# RFStamp.net
KiCad netlist of a schematic drawn in Altium Designer
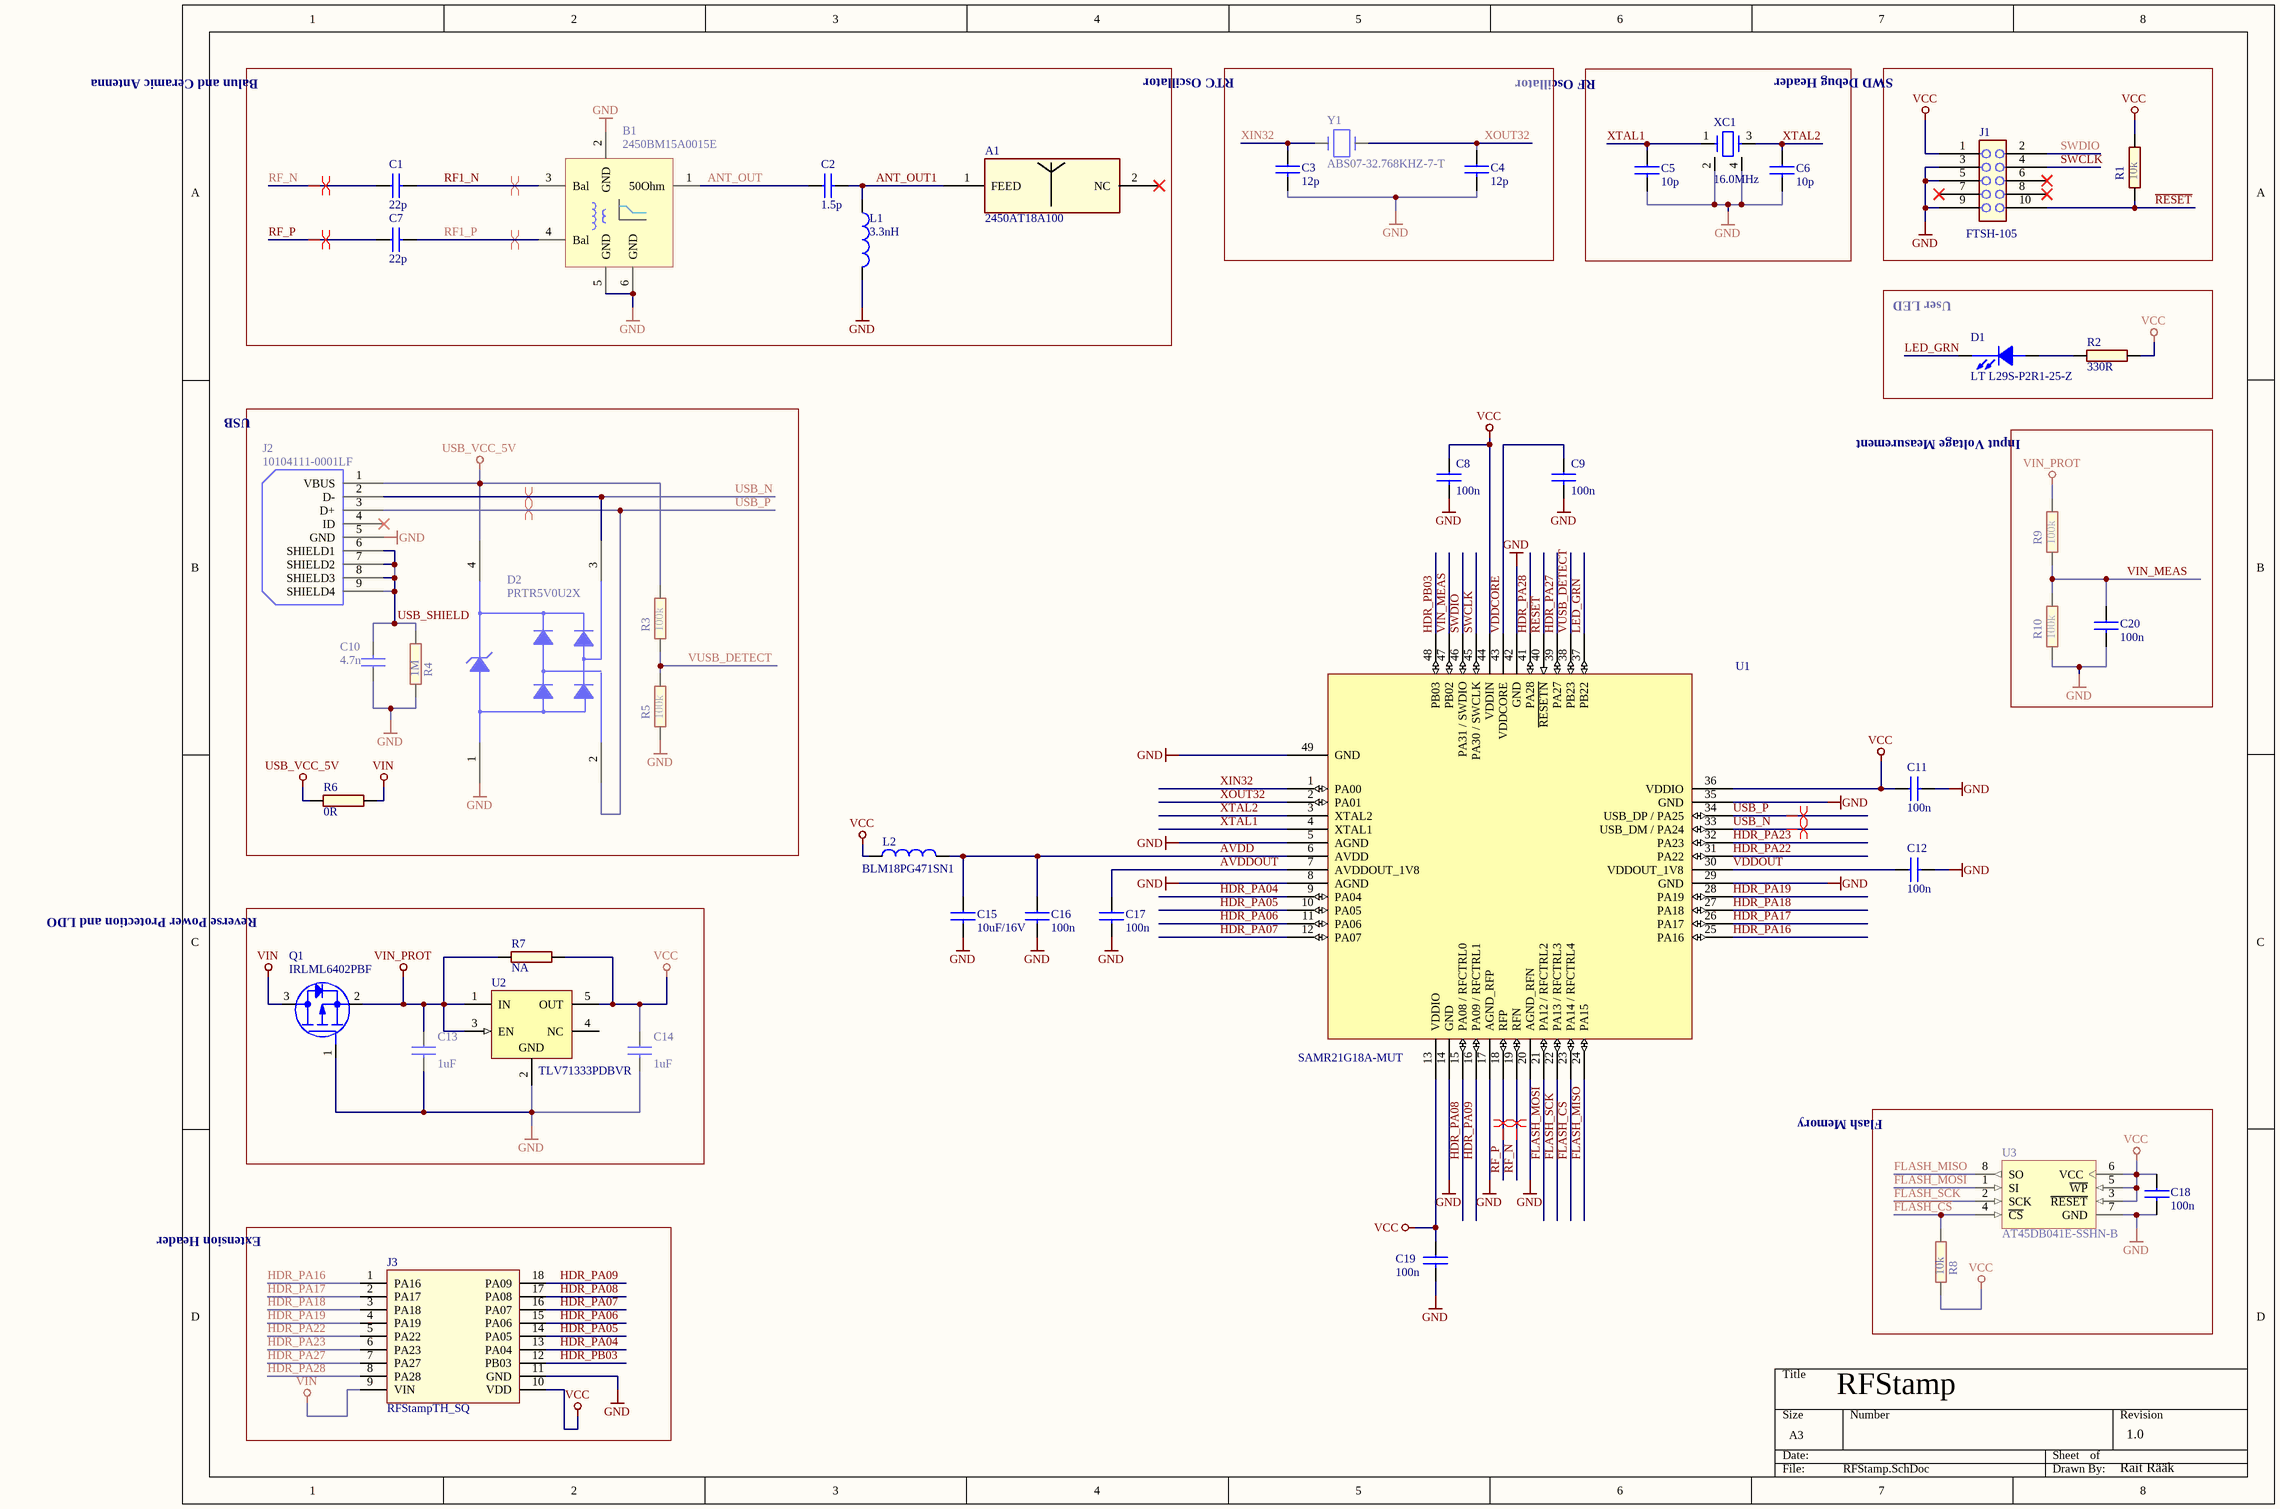
[diagram p0: RFStamp.SchDoc]

(export (version "E")
  (design (tool "Eeschema 10.0.6"))
  (components
    (comp (ref "A1")
      (value "2450AT18A100")
      (footprint "2450AT18A100")
      (description "Ceramic 2.45 GHz Antenna")
      (libsource (lib "Johanson Technology") (part "2450AT18A100"))
    )
    (comp (ref "B1")
      (value "2450BM15A0015E")
      (footprint "SAMR21_Xplained_Pro:AP3-00060")
      (description "Filtered Balun to match AT86RF232/233 (35288)")
      (fields (field (name "MANUFACTURER") "Johanson Technology"))
      (libsource (lib "AltiumDbLib") (part "FilterBalun_NoFeed"))
    )
    (comp (ref "C1")
      (value "22p")
      (footprint "AP1-00053")
      (description "Ceramic capacitor, SMD 0402, X7R, 16V, +/-10%")
      (fields (field (name "TOLERANCE") "16V, +/-10%") (field (name "MANUFACTURER") "Kemet"))
      (libsource (lib "AltiumDbLib") (part "CAP-NONPOL"))
    )
    (comp (ref "C2")
      (value "1.5p")
      (footprint "AP1-00053")
      (description "Ceramic capacitor, SMD 0402, X7R, 16V, +/-10%")
      (fields (field (name "TOLERANCE") "16V, +/-10%") (field (name "MANUFACTURER") "Kemet"))
      (libsource (lib "AltiumDbLib") (part "CAP-NONPOL"))
    )
    (comp (ref "C3")
      (value "12p")
      (footprint "AP1-00053")
      (description "Ceramic capacitor, SMD 0402, X7R, 16V, +/-10%")
      (fields (field (name "TOLERANCE") "16V, +/-10%") (field (name "MANUFACTURER") "Kemet"))
      (libsource (lib "AltiumDbLib") (part "CAP-NONPOL"))
    )
    (comp (ref "C4")
      (value "12p")
      (footprint "AP1-00053")
      (description "Ceramic capacitor, SMD 0402, X7R, 16V, +/-10%")
      (fields (field (name "TOLERANCE") "16V, +/-10%") (field (name "MANUFACTURER") "Kemet"))
      (libsource (lib "AltiumDbLib") (part "CAP-NONPOL"))
    )
    (comp (ref "C5")
      (value "10p")
      (footprint "AP1-00053")
      (description "Ceramic capacitor, SMD 0402, X7R, 16V, +/-10%")
      (fields (field (name "TOLERANCE") "16V, +/-10%") (field (name "MANUFACTURER") "Kemet"))
      (libsource (lib "AltiumDbLib") (part "CAP-NONPOL"))
    )
    (comp (ref "C6")
      (value "10p")
      (footprint "AP1-00053")
      (description "Ceramic capacitor, SMD 0402, X7R, 16V, +/-10%")
      (fields (field (name "TOLERANCE") "16V, +/-10%") (field (name "MANUFACTURER") "Kemet"))
      (libsource (lib "AltiumDbLib") (part "CAP-NONPOL"))
    )
    (comp (ref "C7")
      (value "22p")
      (footprint "AP1-00053")
      (description "Ceramic capacitor, SMD 0402, X7R, 16V, +/-10%")
      (fields (field (name "TOLERANCE") "16V, +/-10%") (field (name "MANUFACTURER") "Kemet"))
      (libsource (lib "AltiumDbLib") (part "CAP-NONPOL"))
    )
    (comp (ref "C8")
      (value "100n")
      (footprint "AP1-00053")
      (description "Ceramic capacitor, SMD 0402, X7R, 16V, +/-10%")
      (fields
        (field (name "TOLERANCE") "16V, +/-10%")
        (field (name "MANUFACTURER") "Kemet")
        (field (name "VERIFIED BY") "Lars Helge Mo")
      )
      (libsource (lib "AltiumDbLib") (part "CAP-NONPOL"))
    )
    (comp (ref "C9")
      (value "100n")
      (footprint "AP1-00053")
      (description "Ceramic capacitor, SMD 0402, X7R, 16V, +/-10%")
      (fields
        (field (name "TOLERANCE") "16V, +/-10%")
        (field (name "MANUFACTURER") "Kemet")
        (field (name "VERIFIED BY") "Lars Helge Mo")
      )
      (libsource (lib "AltiumDbLib") (part "CAP-NONPOL"))
    )
    (comp (ref "C10")
      (value "4.7n")
      (footprint "SAMR21_Xplained_Pro:AP1-00053")
      (description "Ceramic capacitor, SMD 0402, X7R, 25V, +/-10%")
      (fields (field (name "TOLERANCE") "25V, +/-10%"))
      (libsource (lib "AltiumDbLib") (part "CAP-NONPOL"))
    )
    (comp (ref "C11")
      (value "100n")
      (footprint "AP1-00053")
      (description "Ceramic capacitor, SMD 0402, X7R, 16V, +/-10%")
      (fields (field (name "TOLERANCE") "16V, +/-10%") (field (name "MANUFACTURER") "Kemet"))
      (libsource (lib "AltiumDbLib") (part "CAP-NONPOL"))
    )
    (comp (ref "C12")
      (value "100n")
      (footprint "AP1-00053")
      (description "Ceramic capacitor, SMD 0402, X7R, 16V, +/-10%")
      (fields (field (name "TOLERANCE") "16V, +/-10%") (field (name "MANUFACTURER") "Kemet"))
      (libsource (lib "AltiumDbLib") (part "CAP-NONPOL"))
    )
    (comp (ref "C13")
      (value "1uF")
      (footprint "SAMR21_Xplained_Pro:AP1-00039")
      (description "Ceramic capacitor, SMD 0603, X5R, 10V, 10% (de31036)")
      (fields (field (name "TOLERANCE") "10%") (field (name "MANUFACTURER") "tdk"))
      (libsource (lib "AltiumDbLib") (part "CAP-NONPOL"))
    )
    (comp (ref "C14")
      (value "1uF")
      (footprint "SAMR21_Xplained_Pro:AP1-00039")
      (description "Ceramic capacitor, SMD 0603, X5R, 6.3V, 10%")
      (fields (field (name "TOLERANCE") "10%") (field (name "MANUFACTURER") "tdk"))
      (libsource (lib "AltiumDbLib") (part "CAP-NONPOL"))
    )
    (comp (ref "C15")
      (value "10uF/16V")
      (footprint "SAMR21_Xplained_Pro:AP1-00039")
      (description "Ceramic capacitor, SMD 0603, X5R, 16V, 10UF ± 20% (High Density)")
      (fields (field (name "MANUFACTURER") "Taiyo Yuden") (field (name "MPN") "EMK107BBJ106MA-T"))
      (libsource (lib "AltiumDbLib") (part "CAP-NONPOL"))
    )
    (comp (ref "C16")
      (value "100n")
      (footprint "AP1-00053")
      (description "Ceramic capacitor, SMD 0402, X7R, 16V, +/-10%")
      (fields (field (name "TOLERANCE") "16V, +/-10%") (field (name "MANUFACTURER") "Kemet"))
      (libsource (lib "AltiumDbLib") (part "CAP-NONPOL"))
    )
    (comp (ref "C17")
      (value "100n")
      (footprint "AP1-00053")
      (description "Ceramic capacitor, SMD 0402, X7R, 16V, +/-10%")
      (fields (field (name "TOLERANCE") "16V, +/-10%") (field (name "MANUFACTURER") "Kemet"))
      (libsource (lib "AltiumDbLib") (part "CAP-NONPOL"))
    )
    (comp (ref "C18")
      (value "100n")
      (footprint "AP1-00053")
      (description "Ceramic capacitor, SMD 0402, X7R, 16V, +/-10%")
      (fields (field (name "TOLERANCE") "16V, +/-10%") (field (name "MANUFACTURER") "Kemet"))
      (libsource (lib "AltiumDbLib") (part "CAP-NONPOL"))
    )
    (comp (ref "C19")
      (value "100n")
      (footprint "AP1-00053")
      (description "Ceramic capacitor, SMD 0402, X7R, 16V, +/-10%")
      (fields (field (name "TOLERANCE") "16V, +/-10%") (field (name "MANUFACTURER") "Kemet"))
      (libsource (lib "AltiumDbLib") (part "CAP-NONPOL"))
    )
    (comp (ref "C20")
      (value "100n")
      (footprint "AP1-00053")
      (description "Ceramic capacitor, SMD 0402, X7R, 16V, +/-10%")
      (fields (field (name "TOLERANCE") "16V, +/-10%") (field (name "MANUFACTURER") "Kemet"))
      (libsource (lib "AltiumDbLib") (part "CAP-NONPOL"))
    )
    (comp (ref "D1")
      (value "LT L29S-P2R1-25-Z")
      (footprint "Osram:LS L29K")
      (libsource (lib "Osram") (part "LS L29K"))
    )
    (comp (ref "D2")
      (value "PRTR5V0U2X")
      (footprint "SAMR21_Xplained_Pro:AP4-00001")
      (description "Double rail-to-rail USB ESD protection diode")
      (fields (field (name "MANUFACTURER") "Philips"))
      (libsource (lib "AltiumDbLib") (part "PRTR5V0U2X"))
    )
    (comp (ref "J1")
      (value "FTSH-105")
      (footprint "Samtec:FTSH_SMT_10")
      (description "CONN HEADER 10POS DUAL .05\" SMD")
      (libsource (lib "Samtec") (part "FTSH-105"))
    )
    (comp (ref "J2")
      (value "10104111-0001LF")
      (footprint "SAMR21_Xplained_Pro:AP8-00604")
      (description "Micro USB AB Connector")
      (fields (field (name "MANUFACTURER") "FCI"))
      (libsource (lib "AltiumDbLib") (part "USB_AB"))
    )
    (comp (ref "J3")
      (value "RFStampTH_SQ")
      (footprint "RFSTAMP_TH_SQ")
      (libsource (lib "MyLib") (part "RFStampTH_SQ"))
    )
    (comp (ref "L1")
      (value "3.3nH")
      (footprint "0402-A")
      (description "Inductor")
      (libsource (lib "Miscellaneous Devices") (part "Inductor"))
    )
    (comp (ref "L2")
      (value "BLM18PG471SN1")
      (footprint "SAMR21_Xplained_Pro:AP3-00005")
      (description "SMD RF inductor 0603. Z=470Ohm (@100MHz), Max R(dc)=0.65Ohm, Max current=1A")
      (fields (field (name "TOLERANCE") "±25%") (field (name "MANUFACTURER") "Murata"))
      (libsource (lib "AltiumDbLib") (part "INDUCTOR"))
    )
    (comp (ref "Q1")
      (value "IRLML6402PBF")
      (footprint "AP5-00002")
      (description "P-ch. MOSFET. -30V, -3.7A continuous,RDS(ON)=0.05Ohm@VGS=-4,5V, RDS(ON)=0.08Ohm@VGS=-2.5V")
      (fields (field (name "MANUFACTURER") "International Rectifier"))
      (libsource (lib "AltiumDbLib") (part "MOSFET_P_GSD"))
    )
    (comp (ref "R1")
      (value "10k")
      (footprint "AP2-00011")
      (description "Thick film resistor, SMD 0402, 1/16W, 5%")
      (fields (field (name "TOLERANCE") "5 %"))
      (libsource (lib "") (part "R2_2"))
    )
    (comp (ref "R2")
      (value "330R")
      (footprint "AP2-00011")
      (description "Thick film resistor, SMD 0402, 1/16W, 5%")
      (fields (field (name "TOLERANCE") "5 %"))
      (libsource (lib "") (part "R2_3"))
    )
    (comp (ref "R3")
      (value "100k")
      (footprint "AP2-00011")
      (description "Thick film resistor, SMD 0402, 1/16W, 5%")
      (fields (field (name "TOLERANCE") "5 %"))
      (libsource (lib "") (part "R2_2"))
    )
    (comp (ref "R4")
      (value "1M")
      (footprint "SAMR21_Xplained_Pro:AP2-00011")
      (description "Thick film resistor, SMD 0402, 1/16W, 5%")
      (fields (field (name "TOLERANCE") "5 %") (field (name "MANUFACTURER") "KOA"))
      (libsource (lib "AltiumDbLib") (part "R2"))
    )
    (comp (ref "R5")
      (value "100k")
      (footprint "AP2-00011")
      (description "Thick film resistor, SMD 0402, 1/16W, 5%")
      (fields (field (name "TOLERANCE") "5 %"))
      (libsource (lib "") (part "R2_2"))
    )
    (comp (ref "R6")
      (value "0R")
      (footprint "AP2-00011")
      (description "Thick film resistor, SMD 0402, 1/16W, 5%")
      (fields (field (name "TOLERANCE") "5 %"))
      (libsource (lib "") (part "R2_1"))
    )
    (comp (ref "R7")
      (value "NA")
      (footprint "AP2-00011")
      (description "Thick film resistor, SMD 0402, 1/16W, 5%")
      (fields (field (name "TOLERANCE") "5 %") (field (name "Comment") "0R"))
      (libsource (lib "") (part "R2_1"))
    )
    (comp (ref "R8")
      (value "10k")
      (footprint "SAMR21_Xplained_Pro:AP2-00011")
      (description "Thick film resistor, SMD 0402, 1/16W, 5%")
      (fields (field (name "TOLERANCE") "5 %") (field (name "MANUFACTURER") "KOA"))
      (libsource (lib "AltiumDbLib") (part "R2"))
    )
    (comp (ref "R9")
      (value "100k")
      (footprint "AP2-00011")
      (description "Thick film resistor, SMD 0402, 1/16W, 5%")
      (fields (field (name "TOLERANCE") "5 %"))
      (libsource (lib "") (part "R2_2"))
    )
    (comp (ref "R10")
      (value "100k")
      (footprint "AP2-00011")
      (description "Thick film resistor, SMD 0402, 1/16W, 5%")
      (fields (field (name "TOLERANCE") "5 %"))
      (libsource (lib "") (part "R2_2"))
    )
    (comp (ref "U1")
      (value "SAMR21G18A-MUT")
      (footprint "AP6-00171")
      (description "Atmel 32-bit Cortex M0+ MCU with RF233 SIP.")
      (fields (field (name "MANUFACTURER") "ATMEL"))
      (libsource (lib "MyLib") (part "SAMR21G"))
    )
    (comp (ref "U2")
      (value "TLV71333PDBVR")
      (footprint "TI-DBV5_N")
      (fields (field (name "MANUFACTURER") "Texas Instruments"))
      (libsource (lib "TI Power Management Linear Regulator Single Channel LDO (0-350mA)") (part "TLV70233DBVR"))
    )
    (comp (ref "U3")
      (value "AT45DB041E-SSHN-B")
      (footprint "8S1_N")
      (description "4-Mbit DataFlash (with Extra 128-Kbits), 1.65V Minimum SPI Serial Flash Memory, 8-Pin SOIC")
      (libsource (lib "Atmel") (part "AT45DB041E"))
    )
    (comp (ref "XC1")
      (value "16.0MHz")
      (footprint "AP7-00061")
      (description "16MHz uXtal, 3.2 x 2.5 mm SMD, CL=9pF, 15PPM, ESR=80ohm(Max.")
      (fields (field (name "TOLERANCE") "15ppm") (field (name "MANUFACTURER") "Epson Toyocom"))
      (libsource (lib "MyLib") (part "TSX-3225"))
    )
    (comp (ref "Y1")
      (value "ABS07-32.768KHZ-7-T")
      (footprint "ABS07")
      (description "Low Profile Surface Mount Crystal")
      (libsource (lib "Abracon") (part "ABS07"))
    )
  )
  (nets
    (net (code "1") (name "/ANT_OUT") (class "Default")
      (node (ref "B1") (pin "1") (pinfunction "50Ohm_1") (pintype "passive"))
      (node (ref "C2") (pin "1") (pinfunction "1_1") (pintype "passive"))
    )
    (net (code "2") (name "/ANT_OUT1") (class "Default")
      (node (ref "A1") (pin "1") (pinfunction "FEED_1") (pintype "passive"))
      (node (ref "C2") (pin "2") (pinfunction "2_2") (pintype "passive"))
      (node (ref "L1") (pin "1") (pinfunction "1_1") (pintype "passive"))
    )
    (net (code "3") (name "/AVDD") (class "Default")
      (node (ref "C15") (pin "1") (pinfunction "1_1") (pintype "passive"))
      (node (ref "C16") (pin "1") (pinfunction "1_1") (pintype "passive"))
      (node (ref "L2") (pin "2") (pinfunction "2_2") (pintype "passive"))
      (node (ref "U1") (pin "6") (pinfunction "AVDD_6") (pintype "power_in"))
    )
    (net (code "4") (name "/AVDDOUT") (class "Default")
      (node (ref "C17") (pin "1") (pinfunction "1_1") (pintype "passive"))
      (node (ref "U1") (pin "7") (pinfunction "AVDDOUT_1V8_7") (pintype "power_in"))
    )
    (net (code "5") (name "/FLASH_MISO") (class "Default")
      (node (ref "U1") (pin "24") (pinfunction "PA15_24") (pintype "bidirectional"))
      (node (ref "U3") (pin "8") (pinfunction "SO_8") (pintype "output"))
    )
    (net (code "6") (name "/FLASH_MOSI") (class "Default")
      (node (ref "U1") (pin "21") (pinfunction "PA12_/_RFCTRL2_21") (pintype "bidirectional"))
      (node (ref "U3") (pin "1") (pinfunction "SI_1") (pintype "input"))
    )
    (net (code "7") (name "/FLASH_SCK") (class "Default")
      (node (ref "U1") (pin "22") (pinfunction "PA13_/_RFCTRL3_22") (pintype "bidirectional"))
      (node (ref "U3") (pin "2") (pinfunction "SCK_2") (pintype "input"))
    )
    (net (code "8") (name "/HDR_PA04") (class "Default")
      (node (ref "J3") (pin "13") (pinfunction "PA04_13") (pintype "passive"))
      (node (ref "U1") (pin "9") (pinfunction "PA04_9") (pintype "bidirectional"))
    )
    (net (code "9") (name "/HDR_PA05") (class "Default")
      (node (ref "J3") (pin "14") (pinfunction "PA05_14") (pintype "passive"))
      (node (ref "U1") (pin "10") (pinfunction "PA05_10") (pintype "bidirectional"))
    )
    (net (code "10") (name "/HDR_PA06") (class "Default")
      (node (ref "J3") (pin "15") (pinfunction "PA06_15") (pintype "passive"))
      (node (ref "U1") (pin "11") (pinfunction "PA06_11") (pintype "bidirectional"))
    )
    (net (code "11") (name "/HDR_PA07") (class "Default")
      (node (ref "J3") (pin "16") (pinfunction "PA07_16") (pintype "passive"))
      (node (ref "U1") (pin "12") (pinfunction "PA07_12") (pintype "bidirectional"))
    )
    (net (code "12") (name "/HDR_PA08") (class "Default")
      (node (ref "J3") (pin "17") (pinfunction "PA08_17") (pintype "passive"))
      (node (ref "U1") (pin "15") (pinfunction "PA08_/_RFCTRL0_15") (pintype "bidirectional"))
    )
    (net (code "13") (name "/HDR_PA09") (class "Default")
      (node (ref "J3") (pin "18") (pinfunction "PA09_18") (pintype "passive"))
      (node (ref "U1") (pin "16") (pinfunction "PA09_/_RFCTRL1_16") (pintype "bidirectional"))
    )
    (net (code "14") (name "/HDR_PA16") (class "Default")
      (node (ref "J3") (pin "1") (pinfunction "PA16_1") (pintype "passive"))
      (node (ref "U1") (pin "25") (pinfunction "PA16_25") (pintype "bidirectional"))
    )
    (net (code "15") (name "/HDR_PA17") (class "Default")
      (node (ref "J3") (pin "2") (pinfunction "PA17_2") (pintype "passive"))
      (node (ref "U1") (pin "26") (pinfunction "PA17_26") (pintype "bidirectional"))
    )
    (net (code "16") (name "/HDR_PA18") (class "Default")
      (node (ref "J3") (pin "3") (pinfunction "PA18_3") (pintype "passive"))
      (node (ref "U1") (pin "27") (pinfunction "PA18_27") (pintype "bidirectional"))
    )
    (net (code "17") (name "/HDR_PA19") (class "Default")
      (node (ref "J3") (pin "4") (pinfunction "PA19_4") (pintype "passive"))
      (node (ref "U1") (pin "28") (pinfunction "PA19_28") (pintype "bidirectional"))
    )
    (net (code "18") (name "/HDR_PA22") (class "Default")
      (node (ref "J3") (pin "5") (pinfunction "PA22_5") (pintype "passive"))
      (node (ref "U1") (pin "31") (pinfunction "PA22_31") (pintype "bidirectional"))
    )
    (net (code "19") (name "/HDR_PA23") (class "Default")
      (node (ref "J3") (pin "6") (pinfunction "PA23_6") (pintype "passive"))
      (node (ref "U1") (pin "32") (pinfunction "PA23_32") (pintype "bidirectional"))
    )
    (net (code "20") (name "/HDR_PA27") (class "Default")
      (node (ref "J3") (pin "7") (pinfunction "PA27_7") (pintype "passive"))
      (node (ref "U1") (pin "39") (pinfunction "PA27_39") (pintype "bidirectional"))
    )
    (net (code "21") (name "/HDR_PA28") (class "Default")
      (node (ref "J3") (pin "8") (pinfunction "PA28_8") (pintype "passive"))
      (node (ref "U1") (pin "41") (pinfunction "PA28_41") (pintype "bidirectional"))
    )
    (net (code "22") (name "/HDR_PB03") (class "Default")
      (node (ref "J3") (pin "12") (pinfunction "PB03_12") (pintype "passive"))
      (node (ref "U1") (pin "48") (pinfunction "PB03_48") (pintype "bidirectional"))
    )
    (net (code "23") (name "/LED_GRN") (class "Default")
      (node (ref "D1") (pin "1") (pinfunction "CATHODE_1") (pintype "passive"))
      (node (ref "U1") (pin "37") (pinfunction "PB22_37") (pintype "bidirectional"))
    )
    (net (code "24") (name "/RF1_N") (class "Default")
      (node (ref "B1") (pin "3") (pinfunction "Bal_3") (pintype "passive"))
      (node (ref "C1") (pin "2") (pinfunction "2_2") (pintype "passive"))
    )
    (net (code "25") (name "/RF1_P") (class "Default")
      (node (ref "B1") (pin "4") (pinfunction "Bal_4") (pintype "passive"))
      (node (ref "C7") (pin "2") (pinfunction "2_2") (pintype "passive"))
    )
    (net (code "26") (name "/RF_N") (class "Default")
      (node (ref "C1") (pin "1") (pinfunction "1_1") (pintype "passive"))
      (node (ref "U1") (pin "19") (pinfunction "RFN_19") (pintype "bidirectional"))
    )
    (net (code "27") (name "/RF_P") (class "Default")
      (node (ref "C7") (pin "1") (pinfunction "1_1") (pintype "passive"))
      (node (ref "U1") (pin "18") (pinfunction "RFP_18") (pintype "bidirectional"))
    )
    (net (code "28") (name "/SWCLK") (class "Default")
      (node (ref "J1") (pin "4") (pinfunction "4_4") (pintype "passive"))
      (node (ref "U1") (pin "45") (pinfunction "PA30_/_SWCLK_45") (pintype "bidirectional"))
    )
    (net (code "29") (name "/SWDIO") (class "Default")
      (node (ref "J1") (pin "2") (pinfunction "2_2") (pintype "passive"))
      (node (ref "U1") (pin "46") (pinfunction "PA31_/_SWDIO_46") (pintype "bidirectional"))
    )
    (net (code "30") (name "/USB_N") (class "Default")
      (node (ref "D2") (pin "3") (pinfunction "I/O_2_3") (pintype "passive"))
      (node (ref "J2") (pin "2") (pinfunction "D-_2") (pintype "passive"))
      (node (ref "U1") (pin "33") (pinfunction "USB_DM_/_PA24_33") (pintype "bidirectional"))
    )
    (net (code "31") (name "/USB_P") (class "Default")
      (node (ref "D2") (pin "2") (pinfunction "I/O_1_2") (pintype "passive"))
      (node (ref "J2") (pin "3") (pinfunction "D+_3") (pintype "passive"))
      (node (ref "U1") (pin "34") (pinfunction "USB_DP_/_PA25_34") (pintype "bidirectional"))
    )
    (net (code "32") (name "/USB_SHIELD") (class "Default")
      (node (ref "C10") (pin "2") (pinfunction "2_2") (pintype "passive"))
      (node (ref "J2") (pin "6") (pinfunction "SHIELD1_6") (pintype "passive"))
      (node (ref "J2") (pin "7") (pinfunction "SHIELD2_7") (pintype "passive"))
      (node (ref "J2") (pin "8") (pinfunction "SHIELD3_8") (pintype "passive"))
      (node (ref "J2") (pin "9") (pinfunction "SHIELD4_9") (pintype "passive"))
      (node (ref "R4") (pin "2") (pinfunction "2_2") (pintype "passive"))
    )
    (net (code "33") (name "/VDDCORE") (class "Default")
      (node (ref "C9") (pin "1") (pinfunction "1_1") (pintype "passive"))
      (node (ref "U1") (pin "43") (pinfunction "VDDCORE_43") (pintype "power_in"))
    )
    (net (code "34") (name "/VDDOUT") (class "Default")
      (node (ref "C12") (pin "1") (pinfunction "1_1") (pintype "passive"))
      (node (ref "U1") (pin "30") (pinfunction "VDDOUT_1V8_30") (pintype "power_in"))
    )
    (net (code "35") (name "/VIN_MEAS") (class "Default")
      (node (ref "C20") (pin "1") (pinfunction "1_1") (pintype "passive"))
      (node (ref "R10") (pin "2") (pinfunction "2_2") (pintype "passive"))
      (node (ref "R9") (pin "1") (pinfunction "1_1") (pintype "passive"))
      (node (ref "U1") (pin "47") (pinfunction "PB02_47") (pintype "bidirectional"))
    )
    (net (code "36") (name "/VUSB_DETECT") (class "Default")
      (node (ref "R3") (pin "1") (pinfunction "1_1") (pintype "passive"))
      (node (ref "R5") (pin "2") (pinfunction "2_2") (pintype "passive"))
      (node (ref "U1") (pin "38") (pinfunction "PB23_38") (pintype "bidirectional"))
    )
    (net (code "37") (name "/XIN32") (class "Default")
      (node (ref "C3") (pin "1") (pinfunction "1_1") (pintype "passive"))
      (node (ref "U1") (pin "1") (pinfunction "PA00_1") (pintype "bidirectional"))
      (node (ref "Y1") (pin "1") (pinfunction "1_1") (pintype "passive"))
    )
    (net (code "38") (name "/XOUT32") (class "Default")
      (node (ref "C4") (pin "1") (pinfunction "1_1") (pintype "passive"))
      (node (ref "U1") (pin "2") (pinfunction "PA01_2") (pintype "bidirectional"))
      (node (ref "Y1") (pin "2") (pinfunction "2_2") (pintype "passive"))
    )
    (net (code "39") (name "/XTAL1") (class "Default")
      (node (ref "C5") (pin "1") (pinfunction "1_1") (pintype "passive"))
      (node (ref "U1") (pin "4") (pinfunction "XTAL1_4") (pintype "passive"))
      (node (ref "XC1") (pin "1") (pinfunction "IN_1") (pintype "passive"))
    )
    (net (code "40") (name "/XTAL2") (class "Default")
      (node (ref "C6") (pin "1") (pinfunction "1_1") (pintype "passive"))
      (node (ref "U1") (pin "3") (pinfunction "XTAL2_3") (pintype "passive"))
      (node (ref "XC1") (pin "3") (pinfunction "OUT_3") (pintype "passive"))
    )
    (net (code "41") (name "/~{FLASH_CS}") (class "Default")
      (node (ref "R8") (pin "2") (pinfunction "2_2") (pintype "passive"))
      (node (ref "U1") (pin "23") (pinfunction "PA14_/_RFCTRL4_23") (pintype "bidirectional"))
      (node (ref "U3") (pin "4") (pinfunction "~{CS}_4") (pintype "input"))
    )
    (net (code "42") (name "/~{RESET}") (class "Default")
      (node (ref "J1") (pin "10") (pinfunction "10_10") (pintype "passive"))
      (node (ref "R1") (pin "1") (pinfunction "1_1") (pintype "passive"))
      (node (ref "U1") (pin "40") (pinfunction "~{RESETN}_40") (pintype "input"))
    )
    (net (code "43") (name "GND") (class "Default")
      (node (ref "B1") (pin "2") (pinfunction "GND_2") (pintype "power_in"))
      (node (ref "B1") (pin "5") (pinfunction "GND_5") (pintype "power_in"))
      (node (ref "B1") (pin "6") (pinfunction "GND_6") (pintype "passive"))
      (node (ref "C10") (pin "1") (pinfunction "1_1") (pintype "passive"))
      (node (ref "C11") (pin "2") (pinfunction "2_2") (pintype "passive"))
      (node (ref "C12") (pin "2") (pinfunction "2_2") (pintype "passive"))
      (node (ref "C13") (pin "2") (pinfunction "2_2") (pintype "passive"))
      (node (ref "C14") (pin "2") (pinfunction "2_2") (pintype "passive"))
      (node (ref "C15") (pin "2") (pinfunction "2_2") (pintype "passive"))
      (node (ref "C16") (pin "2") (pinfunction "2_2") (pintype "passive"))
      (node (ref "C17") (pin "2") (pinfunction "2_2") (pintype "passive"))
      (node (ref "C18") (pin "2") (pinfunction "2_2") (pintype "passive"))
      (node (ref "C19") (pin "2") (pinfunction "2_2") (pintype "passive"))
      (node (ref "C20") (pin "2") (pinfunction "2_2") (pintype "passive"))
      (node (ref "C3") (pin "2") (pinfunction "2_2") (pintype "passive"))
      (node (ref "C4") (pin "2") (pinfunction "2_2") (pintype "passive"))
      (node (ref "C5") (pin "2") (pinfunction "2_2") (pintype "passive"))
      (node (ref "C6") (pin "2") (pinfunction "2_2") (pintype "passive"))
      (node (ref "C8") (pin "2") (pinfunction "2_2") (pintype "passive"))
      (node (ref "C9") (pin "2") (pinfunction "2_2") (pintype "passive"))
      (node (ref "D2") (pin "1") (pinfunction "GND_1") (pintype "passive"))
      (node (ref "J1") (pin "3") (pinfunction "3_3") (pintype "passive"))
      (node (ref "J1") (pin "5") (pinfunction "5_5") (pintype "passive"))
      (node (ref "J1") (pin "9") (pinfunction "9_9") (pintype "passive"))
      (node (ref "J2") (pin "5") (pinfunction "GND_5") (pintype "passive"))
      (node (ref "J3") (pin "11") (pinfunction "GND_11") (pintype "passive"))
      (node (ref "L1") (pin "2") (pinfunction "2_2") (pintype "passive"))
      (node (ref "Q1") (pin "1") (pinfunction "G_1") (pintype "passive"))
      (node (ref "R10") (pin "1") (pinfunction "1_1") (pintype "passive"))
      (node (ref "R4") (pin "1") (pinfunction "1_1") (pintype "passive"))
      (node (ref "R5") (pin "1") (pinfunction "1_1") (pintype "passive"))
      (node (ref "U1") (pin "14") (pinfunction "GND_14") (pintype "power_in"))
      (node (ref "U1") (pin "17") (pinfunction "AGND_RFP_17") (pintype "power_in"))
      (node (ref "U1") (pin "20") (pinfunction "AGND_RFN_20") (pintype "power_in"))
      (node (ref "U1") (pin "29") (pinfunction "GND_29") (pintype "power_in"))
      (node (ref "U1") (pin "35") (pinfunction "GND_35") (pintype "power_in"))
      (node (ref "U1") (pin "42") (pinfunction "GND_42") (pintype "power_in"))
      (node (ref "U1") (pin "49") (pinfunction "GND_49") (pintype "power_in"))
      (node (ref "U1") (pin "5") (pinfunction "AGND_5") (pintype "power_in"))
      (node (ref "U1") (pin "8") (pinfunction "AGND_8") (pintype "power_in"))
      (node (ref "U2") (pin "2") (pinfunction "GND_2") (pintype "power_in"))
      (node (ref "U3") (pin "7") (pinfunction "GND_7") (pintype "power_in"))
      (node (ref "XC1") (pin "2") (pinfunction "GND_2") (pintype "passive"))
      (node (ref "XC1") (pin "4") (pinfunction "GND_4") (pintype "passive"))
    )
    (net (code "44") (name "Net-(D1-ANODE)") (class "Default")
      (node (ref "D1") (pin "2") (pinfunction "ANODE_2") (pintype "passive"))
      (node (ref "R2") (pin "2") (pinfunction "2_2") (pintype "passive"))
    )
    (net (code "45") (name "USB_VCC_5V") (class "Default")
      (node (ref "D2") (pin "4") (pinfunction "VCC_4") (pintype "passive"))
      (node (ref "J2") (pin "1") (pinfunction "VBUS_1") (pintype "passive"))
      (node (ref "R3") (pin "2") (pinfunction "2_2") (pintype "passive"))
      (node (ref "R6") (pin "2") (pinfunction "2_2") (pintype "passive"))
    )
    (net (code "46") (name "VCC") (class "Default")
      (node (ref "C11") (pin "1") (pinfunction "1_1") (pintype "passive"))
      (node (ref "C14") (pin "1") (pinfunction "1_1") (pintype "passive"))
      (node (ref "C18") (pin "1") (pinfunction "1_1") (pintype "passive"))
      (node (ref "C19") (pin "1") (pinfunction "1_1") (pintype "passive"))
      (node (ref "C8") (pin "1") (pinfunction "1_1") (pintype "passive"))
      (node (ref "J1") (pin "1") (pinfunction "1_1") (pintype "passive"))
      (node (ref "J3") (pin "10") (pinfunction "VDD_10") (pintype "passive"))
      (node (ref "L2") (pin "1") (pinfunction "1_1") (pintype "passive"))
      (node (ref "R1") (pin "2") (pinfunction "2_2") (pintype "passive"))
      (node (ref "R2") (pin "1") (pinfunction "1_1") (pintype "passive"))
      (node (ref "R7") (pin "1") (pinfunction "1_1") (pintype "passive"))
      (node (ref "R8") (pin "1") (pinfunction "1_1") (pintype "passive"))
      (node (ref "U1") (pin "13") (pinfunction "VDDIO_13") (pintype "power_in"))
      (node (ref "U1") (pin "36") (pinfunction "VDDIO_36") (pintype "power_in"))
      (node (ref "U1") (pin "44") (pinfunction "VDDIN_44") (pintype "power_in"))
      (node (ref "U2") (pin "5") (pinfunction "OUT_5") (pintype "power_in"))
      (node (ref "U3") (pin "3") (pinfunction "~{RESET}_3") (pintype "input"))
      (node (ref "U3") (pin "5") (pinfunction "~{WP}_5") (pintype "input"))
      (node (ref "U3") (pin "6") (pinfunction "VCC_6") (pintype "power_in"))
    )
    (net (code "47") (name "VIN") (class "Default")
      (node (ref "J3") (pin "9") (pinfunction "VIN_9") (pintype "passive"))
      (node (ref "Q1") (pin "3") (pinfunction "D_3") (pintype "passive"))
      (node (ref "R6") (pin "1") (pinfunction "1_1") (pintype "passive"))
    )
    (net (code "48") (name "VIN_PROT") (class "Default")
      (node (ref "C13") (pin "1") (pinfunction "1_1") (pintype "passive"))
      (node (ref "Q1") (pin "2") (pinfunction "S_2") (pintype "passive"))
      (node (ref "R7") (pin "2") (pinfunction "2_2") (pintype "passive"))
      (node (ref "R9") (pin "2") (pinfunction "2_2") (pintype "passive"))
      (node (ref "U2") (pin "1") (pinfunction "IN_1") (pintype "power_in"))
      (node (ref "U2") (pin "3") (pinfunction "EN_3") (pintype "input"))
    )
    (net (code "49") (name "unconnected-(A1-NC-Pad2)") (class "Default")
      (node (ref "A1") (pin "2") (pinfunction "NC_2") (pintype "passive+no_connect"))
    )
    (net (code "50") (name "unconnected-(J1-Pad6)") (class "Default")
      (node (ref "J1") (pin "6") (pinfunction "6_6") (pintype "passive+no_connect"))
    )
    (net (code "51") (name "unconnected-(J1-Pad7)") (class "Default")
      (node (ref "J1") (pin "7") (pinfunction "7_7") (pintype "passive+no_connect"))
    )
    (net (code "52") (name "unconnected-(J1-Pad8)") (class "Default")
      (node (ref "J1") (pin "8") (pinfunction "8_8") (pintype "passive+no_connect"))
    )
    (net (code "53") (name "unconnected-(J2-ID-Pad4)") (class "Default")
      (node (ref "J2") (pin "4") (pinfunction "ID_4") (pintype "passive+no_connect"))
    )
    (net (code "54") (name "unconnected-(U2-NC-Pad4)") (class "Default")
      (node (ref "U2") (pin "4") (pinfunction "NC_4") (pintype "passive"))
    )
  )
)
